# Etch_a_Sketch.net
KiCad netlist of a schematic drawn in EAGLE
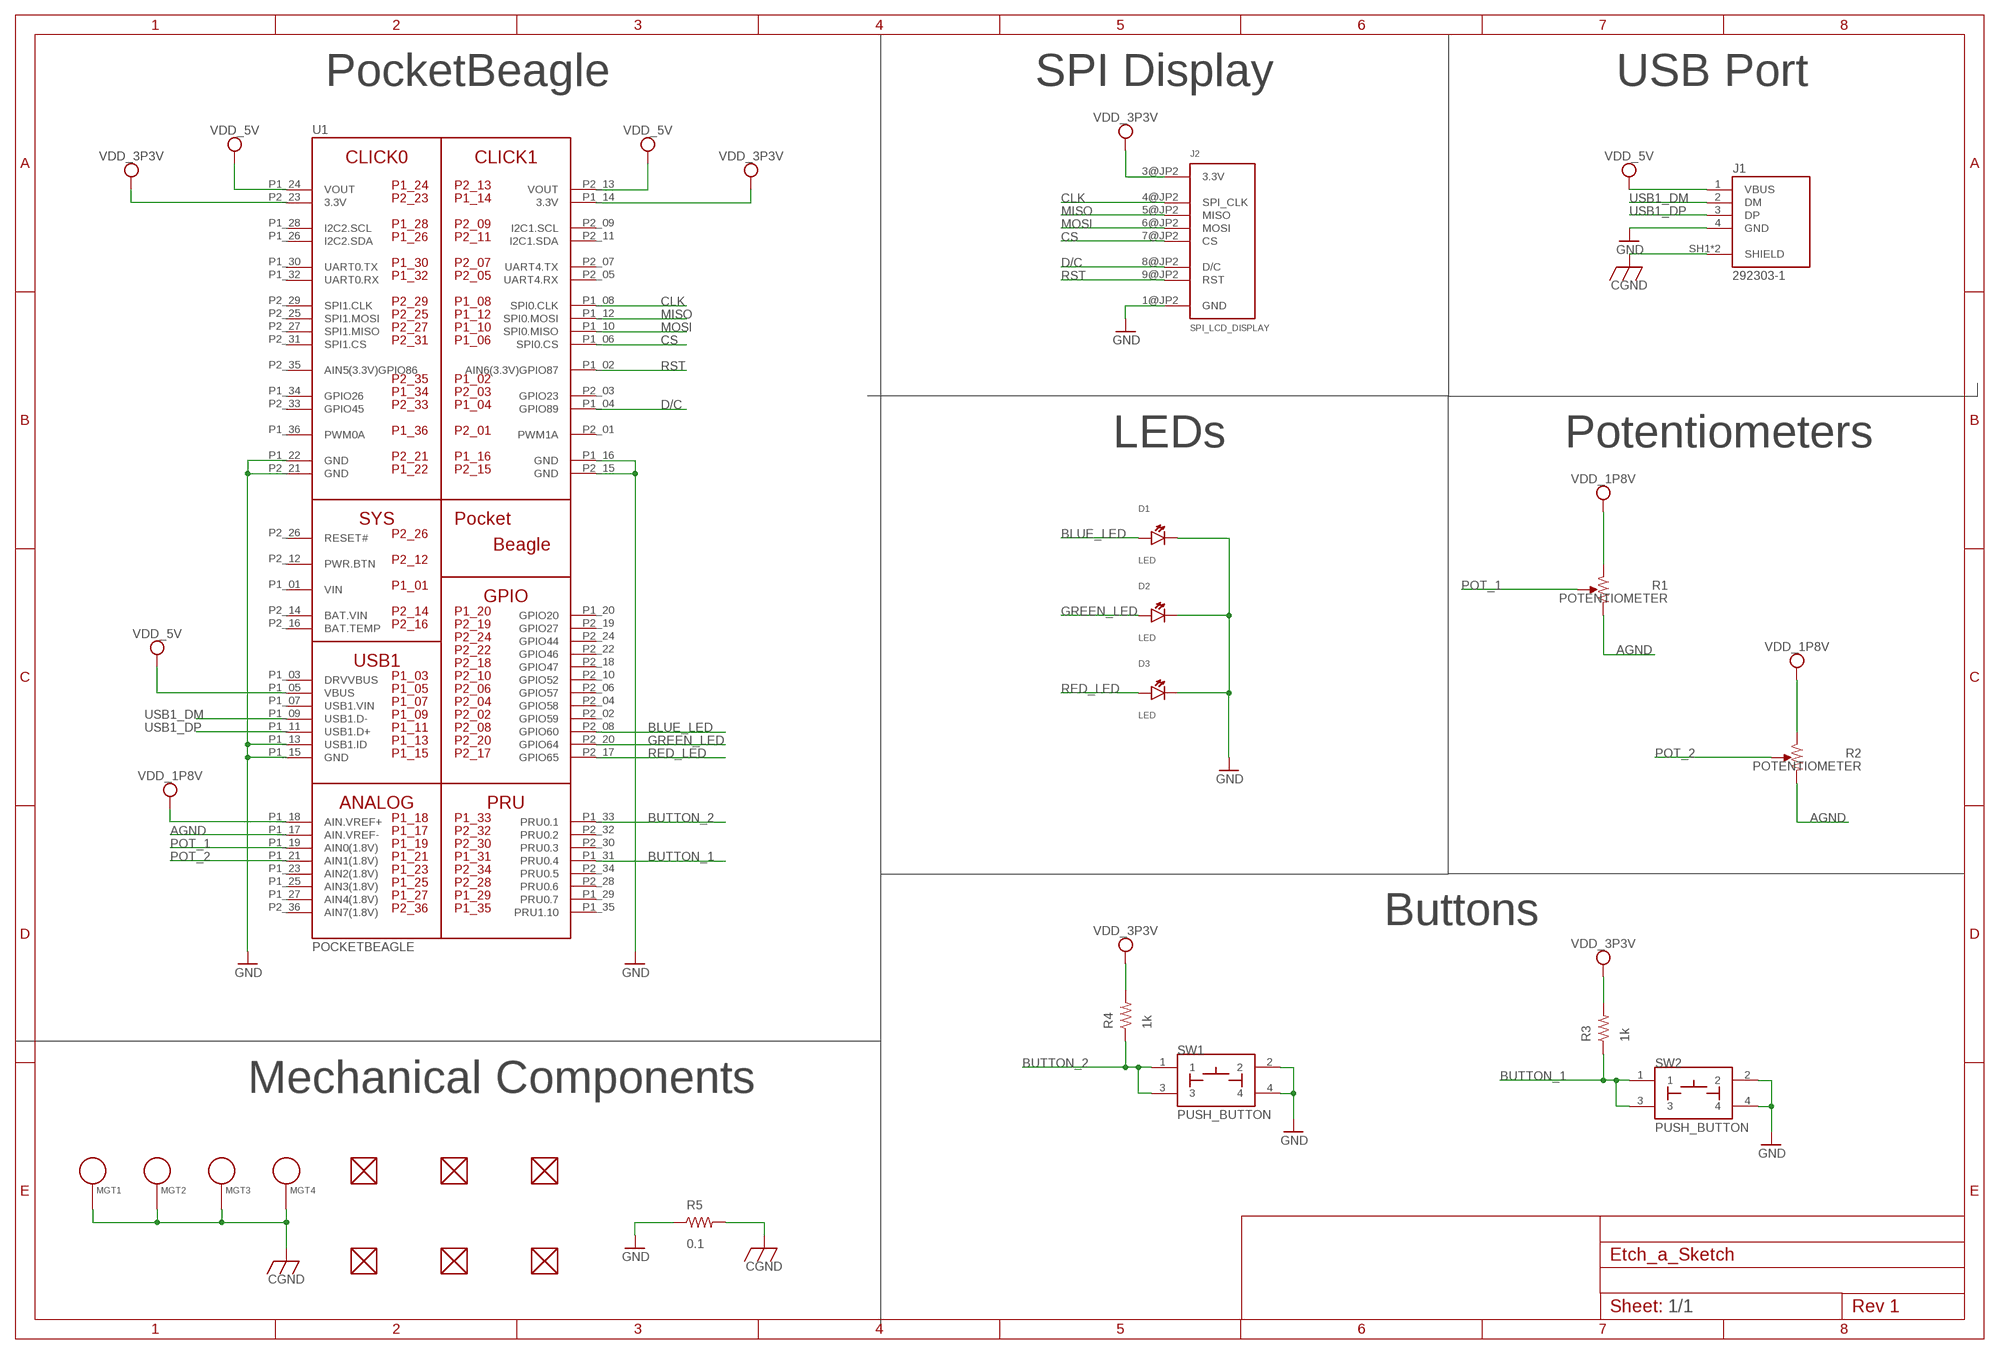
[diagram p0: schematic, sheet 1]

(export (version "E")
  (design (tool "Eeschema 10.0.6"))
  (components
    (comp (ref "D1")
      (value "LED")
      (footprint "eagle-import:EIA-STD")
      (libsource (lib "eagle-import") (part "LED"))
    )
    (comp (ref "D2")
      (value "LED")
      (footprint "eagle-import:EIA-STD")
      (libsource (lib "eagle-import") (part "LED"))
    )
    (comp (ref "D3")
      (value "LED")
      (footprint "eagle-import:EIA-STD")
      (libsource (lib "eagle-import") (part "LED"))
    )
    (comp (ref "FUD1")
      (value "FIDUCIAL")
      (footprint "eagle-import:FIDUCIAL_40MIL")
      (libsource (lib "eagle-import") (part "FIDUCIAL"))
    )
    (comp (ref "FUD2")
      (value "FIDUCIAL")
      (footprint "eagle-import:FIDUCIAL_40MIL")
      (libsource (lib "eagle-import") (part "FIDUCIAL"))
    )
    (comp (ref "FUD3")
      (value "FIDUCIAL")
      (footprint "eagle-import:FIDUCIAL_40MIL")
      (libsource (lib "eagle-import") (part "FIDUCIAL"))
    )
    (comp (ref "FUD4")
      (value "FIDUCIAL")
      (footprint "eagle-import:FIDUCIAL_40MIL")
      (libsource (lib "eagle-import") (part "FIDUCIAL"))
    )
    (comp (ref "FUD5")
      (value "FIDUCIAL")
      (footprint "eagle-import:FIDUCIAL_40MIL")
      (libsource (lib "eagle-import") (part "FIDUCIAL"))
    )
    (comp (ref "FUD6")
      (value "FIDUCIAL")
      (footprint "eagle-import:FIDUCIAL_40MIL")
      (libsource (lib "eagle-import") (part "FIDUCIAL"))
    )
    (comp (ref "J1")
      (value "292303-1")
      (footprint "eagle-import:TE_292303-1")
      (fields (field (name "MF") "TE Connectivity"))
      (libsource (lib "eagle-import") (part "292303-1"))
    )
    (comp (ref "J2")
      (value "SPI_LCD_DISPLAY")
      (footprint "eagle-import:SPI_LCD_DISPLAY")
      (libsource (lib "eagle-import") (part "SPI_LCD_DISPLAY"))
    )
    (comp (ref "MGT1")
      (value "MOUNTING_HOLE")
      (footprint "eagle-import:MOUNTING_HOLE")
      (libsource (lib "eagle-import") (part "MOUNTING_HOLE"))
    )
    (comp (ref "MGT2")
      (value "MOUNTING_HOLE")
      (footprint "eagle-import:MOUNTING_HOLE")
      (libsource (lib "eagle-import") (part "MOUNTING_HOLE"))
    )
    (comp (ref "MGT3")
      (value "MOUNTING_HOLE")
      (footprint "eagle-import:MOUNTING_HOLE")
      (libsource (lib "eagle-import") (part "MOUNTING_HOLE"))
    )
    (comp (ref "MGT4")
      (value "MOUNTING_HOLE")
      (footprint "eagle-import:MOUNTING_HOLE")
      (libsource (lib "eagle-import") (part "MOUNTING_HOLE"))
    )
    (comp (ref "R1")
      (value "POTENTIOMETER")
      (footprint "eagle-import:POT-PO90S")
      (libsource (lib "eagle-import") (part "POTENTIOMETER"))
    )
    (comp (ref "R2")
      (value "POTENTIOMETER")
      (footprint "eagle-import:POT-PO90S")
      (libsource (lib "eagle-import") (part "POTENTIOMETER"))
    )
    (comp (ref "R3")
      (value "1k")
      (footprint "eagle-import:R0603")
      (libsource (lib "eagle-import") (part "R_R0603"))
    )
    (comp (ref "R4")
      (value "1k")
      (footprint "eagle-import:R0603")
      (libsource (lib "eagle-import") (part "R_R0603"))
    )
    (comp (ref "R5")
      (value "0.1")
      (footprint "eagle-import:R0603")
      (libsource (lib "eagle-import") (part "R_R0603"))
    )
    (comp (ref "SW1")
      (value "PUSH_BUTTON")
      (footprint "eagle-import:BUTTON_12.5MM")
      (libsource (lib "eagle-import") (part "PUSH_BUTTON"))
    )
    (comp (ref "SW2")
      (value "PUSH_BUTTON")
      (footprint "eagle-import:BUTTON_12.5MM")
      (libsource (lib "eagle-import") (part "PUSH_BUTTON"))
    )
    (comp (ref "U1")
      (value "POCKETBEAGLE")
      (footprint "eagle-import:POCKETBEAGLE")
      (libsource (lib "eagle-import") (part "POCKETBEAGLE"))
    )
  )
  (nets
    (net (code "1") (name "/AGND") (class "Default")
      (node (ref "R1") (pin "CW") (pinfunction "CW_CW") (pintype "passive"))
      (node (ref "R2") (pin "CW") (pinfunction "CW_CW") (pintype "passive"))
      (node (ref "U1") (pin "P1_17") (pinfunction "AIN.VREF-_P1_17") (pintype "input"))
    )
    (net (code "2") (name "/BAT.VIN") (class "Default")
      (node (ref "U1") (pin "P2_14") (pinfunction "BAT.VIN_P2_14") (pintype "power_in"))
    )
    (net (code "3") (name "/BLUE_LED") (class "Default")
      (node (ref "D1") (pin "ANODE") (pinfunction "ANODE_ANODE") (pintype "bidirectional"))
      (node (ref "U1") (pin "P2_08") (pinfunction "GPIO60_P2_08") (pintype "bidirectional"))
    )
    (net (code "4") (name "/BUTTON_1") (class "Default")
      (node (ref "R3") (pin "1") (pinfunction "1_1") (pintype "passive"))
      (node (ref "SW2") (pin "1") (pinfunction "1_1") (pintype "bidirectional"))
      (node (ref "SW2") (pin "3") (pinfunction "3_3") (pintype "bidirectional"))
      (node (ref "U1") (pin "P1_31") (pinfunction "PRU0.4_P1_31") (pintype "bidirectional"))
    )
    (net (code "5") (name "/BUTTON_2") (class "Default")
      (node (ref "R4") (pin "1") (pinfunction "1_1") (pintype "passive"))
      (node (ref "SW1") (pin "1") (pinfunction "1_1") (pintype "bidirectional"))
      (node (ref "SW1") (pin "3") (pinfunction "3_3") (pintype "bidirectional"))
      (node (ref "U1") (pin "P1_33") (pinfunction "PRU0.1_P1_33") (pintype "bidirectional"))
    )
    (net (code "6") (name "/CLK") (class "Default")
      (node (ref "J2") (pin "4@JP2") (pinfunction "SPI_CLK_4@JP2") (pintype "bidirectional"))
      (node (ref "U1") (pin "P1_08") (pinfunction "SPI0.CLK_P1_08") (pintype "bidirectional"))
    )
    (net (code "7") (name "/CS") (class "Default")
      (node (ref "J2") (pin "7@JP2") (pinfunction "CS_7@JP2") (pintype "bidirectional"))
      (node (ref "U1") (pin "P1_06") (pinfunction "SPI0.CS_P1_06") (pintype "bidirectional"))
    )
    (net (code "8") (name "/D{slash}C") (class "Default")
      (node (ref "J2") (pin "8@JP2") (pinfunction "D/C_8@JP2") (pintype "bidirectional"))
      (node (ref "U1") (pin "P1_04") (pinfunction "GPIO89_P1_04") (pintype "bidirectional"))
    )
    (net (code "9") (name "/GREEN_LED") (class "Default")
      (node (ref "D2") (pin "ANODE") (pinfunction "ANODE_ANODE") (pintype "bidirectional"))
      (node (ref "U1") (pin "P2_20") (pinfunction "GPIO64_P2_20") (pintype "bidirectional"))
    )
    (net (code "10") (name "/MISO") (class "Default")
      (node (ref "J2") (pin "5@JP2") (pinfunction "MISO_5@JP2") (pintype "bidirectional"))
      (node (ref "U1") (pin "P1_12") (pinfunction "SPI0.MOSI_P1_12") (pintype "bidirectional"))
    )
    (net (code "11") (name "/MOSI") (class "Default")
      (node (ref "J2") (pin "6@JP2") (pinfunction "MOSI_6@JP2") (pintype "bidirectional"))
      (node (ref "U1") (pin "P1_10") (pinfunction "SPI0.MISO_P1_10") (pintype "bidirectional"))
    )
    (net (code "12") (name "/POT_1") (class "Default")
      (node (ref "R1") (pin "S") (pinfunction "S_S") (pintype "bidirectional"))
      (node (ref "U1") (pin "P1_19") (pinfunction "AIN0(1.8V)_P1_19") (pintype "input"))
    )
    (net (code "13") (name "/POT_2") (class "Default")
      (node (ref "R2") (pin "S") (pinfunction "S_S") (pintype "bidirectional"))
      (node (ref "U1") (pin "P1_21") (pinfunction "AIN1(1.8V)_P1_21") (pintype "input"))
    )
    (net (code "14") (name "/RED_LED") (class "Default")
      (node (ref "D3") (pin "ANODE") (pinfunction "ANODE_ANODE") (pintype "bidirectional"))
      (node (ref "U1") (pin "P2_17") (pinfunction "GPIO65_P2_17") (pintype "bidirectional"))
    )
    (net (code "15") (name "/RST") (class "Default")
      (node (ref "J2") (pin "9@JP2") (pinfunction "RST_9@JP2") (pintype "bidirectional"))
      (node (ref "U1") (pin "P1_02") (pinfunction "AIN6(3.3V)GPIO87_P1_02") (pintype "bidirectional"))
    )
    (net (code "16") (name "/USB1_DM") (class "Default")
      (node (ref "J1") (pin "2") (pinfunction "DM_2") (pintype "passive"))
      (node (ref "U1") (pin "P1_09") (pinfunction "USB1.D-_P1_09") (pintype "bidirectional"))
    )
    (net (code "17") (name "/USB1_DP") (class "Default")
      (node (ref "J1") (pin "3") (pinfunction "DP_3") (pintype "passive"))
      (node (ref "U1") (pin "P1_11") (pinfunction "USB1.D+_P1_11") (pintype "bidirectional"))
    )
    (net (code "18") (name "/VIN") (class "Default")
      (node (ref "U1") (pin "P1_01") (pinfunction "VIN_P1_01") (pintype "power_in"))
    )
    (net (code "19") (name "CGND") (class "Default")
      (node (ref "J1") (pin "SH1") (pinfunction "SHIELD_SH1") (pintype "passive"))
      (node (ref "J1") (pin "SH2") (pinfunction "SHIELD_SH2") (pintype "passive"))
      (node (ref "MGT1") (pin "P$1") (pinfunction "P$1_P$1") (pintype "bidirectional"))
      (node (ref "MGT2") (pin "P$1") (pinfunction "P$1_P$1") (pintype "bidirectional"))
      (node (ref "MGT3") (pin "P$1") (pinfunction "P$1_P$1") (pintype "bidirectional"))
      (node (ref "MGT4") (pin "P$1") (pinfunction "P$1_P$1") (pintype "bidirectional"))
      (node (ref "R5") (pin "2") (pinfunction "2_2") (pintype "passive"))
    )
    (net (code "20") (name "GND") (class "Default")
      (node (ref "D1") (pin "CATHODE") (pinfunction "CATHODE_CATHODE") (pintype "bidirectional"))
      (node (ref "D2") (pin "CATHODE") (pinfunction "CATHODE_CATHODE") (pintype "bidirectional"))
      (node (ref "D3") (pin "CATHODE") (pinfunction "CATHODE_CATHODE") (pintype "bidirectional"))
      (node (ref "J1") (pin "4") (pinfunction "GND_4") (pintype "passive"))
      (node (ref "J2") (pin "1@JP2") (pinfunction "GND_1@JP2") (pintype "bidirectional"))
      (node (ref "R5") (pin "1") (pinfunction "1_1") (pintype "passive"))
      (node (ref "SW1") (pin "2") (pinfunction "2_2") (pintype "bidirectional"))
      (node (ref "SW1") (pin "4") (pinfunction "4_4") (pintype "bidirectional"))
      (node (ref "SW2") (pin "2") (pinfunction "2_2") (pintype "bidirectional"))
      (node (ref "SW2") (pin "4") (pinfunction "4_4") (pintype "bidirectional"))
      (node (ref "U1") (pin "P1_13") (pinfunction "USB1.ID_P1_13") (pintype "bidirectional"))
      (node (ref "U1") (pin "P1_15") (pinfunction "GND_P1_15") (pintype "bidirectional"))
      (node (ref "U1") (pin "P1_16") (pinfunction "GND_P1_16") (pintype "power_in"))
      (node (ref "U1") (pin "P1_22") (pinfunction "GND_P1_22") (pintype "power_in"))
      (node (ref "U1") (pin "P2_15") (pinfunction "GND_P2_15") (pintype "power_in"))
      (node (ref "U1") (pin "P2_21") (pinfunction "GND_P2_21") (pintype "power_in"))
    )
    (net (code "21") (name "VDD_1P8V") (class "Default")
      (node (ref "R1") (pin "CCW") (pinfunction "CCW_CCW") (pintype "passive"))
      (node (ref "R2") (pin "CCW") (pinfunction "CCW_CCW") (pintype "passive"))
      (node (ref "U1") (pin "P1_18") (pinfunction "AIN.VREF+_P1_18") (pintype "input"))
    )
    (net (code "22") (name "VDD_3P3V") (class "Default")
      (node (ref "J2") (pin "3@JP2") (pinfunction "3.3V_3@JP2") (pintype "bidirectional"))
      (node (ref "R3") (pin "2") (pinfunction "2_2") (pintype "passive"))
      (node (ref "R4") (pin "2") (pinfunction "2_2") (pintype "passive"))
      (node (ref "U1") (pin "P1_14") (pinfunction "3.3V_P1_14") (pintype "power_in"))
      (node (ref "U1") (pin "P2_23") (pinfunction "3.3V_P2_23") (pintype "power_in"))
    )
    (net (code "23") (name "VDD_5V") (class "Default")
      (node (ref "J1") (pin "1") (pinfunction "VBUS_1") (pintype "passive"))
      (node (ref "U1") (pin "P1_05") (pinfunction "VBUS_P1_05") (pintype "bidirectional"))
      (node (ref "U1") (pin "P1_24") (pinfunction "VOUT_P1_24") (pintype "power_in"))
      (node (ref "U1") (pin "P2_13") (pinfunction "VOUT_P2_13") (pintype "power_in"))
    )
    (net (code "24") (name "unconnected-(FUD1-PadP$1)") (class "Default")
      (node (ref "FUD1") (pin "P$1") (pinfunction "P$1_P$1") (pintype "no_connect"))
    )
    (net (code "25") (name "unconnected-(FUD2-PadP$1)") (class "Default")
      (node (ref "FUD2") (pin "P$1") (pinfunction "P$1_P$1") (pintype "no_connect"))
    )
    (net (code "26") (name "unconnected-(FUD3-PadP$1)") (class "Default")
      (node (ref "FUD3") (pin "P$1") (pinfunction "P$1_P$1") (pintype "no_connect"))
    )
    (net (code "27") (name "unconnected-(FUD4-PadP$1)") (class "Default")
      (node (ref "FUD4") (pin "P$1") (pinfunction "P$1_P$1") (pintype "no_connect"))
    )
    (net (code "28") (name "unconnected-(FUD5-PadP$1)") (class "Default")
      (node (ref "FUD5") (pin "P$1") (pinfunction "P$1_P$1") (pintype "no_connect"))
    )
    (net (code "29") (name "unconnected-(FUD6-PadP$1)") (class "Default")
      (node (ref "FUD6") (pin "P$1") (pinfunction "P$1_P$1") (pintype "no_connect"))
    )
    (net (code "30") (name "unconnected-(U1-AIN2(1.8V)-PadP1_23)") (class "Default")
      (node (ref "U1") (pin "P1_23") (pinfunction "AIN2(1.8V)_P1_23") (pintype "input"))
    )
    (net (code "31") (name "unconnected-(U1-AIN3(1.8V)-PadP1_25)") (class "Default")
      (node (ref "U1") (pin "P1_25") (pinfunction "AIN3(1.8V)_P1_25") (pintype "input"))
    )
    (net (code "32") (name "unconnected-(U1-AIN4(1.8V)-PadP1_27)") (class "Default")
      (node (ref "U1") (pin "P1_27") (pinfunction "AIN4(1.8V)_P1_27") (pintype "input"))
    )
    (net (code "33") (name "unconnected-(U1-AIN5(3.3V)GPIO86-PadP2_35)") (class "Default")
      (node (ref "U1") (pin "P2_35") (pinfunction "AIN5(3.3V)GPIO86_P2_35") (pintype "bidirectional"))
    )
    (net (code "34") (name "unconnected-(U1-AIN7(1.8V)-PadP2_36)") (class "Default")
      (node (ref "U1") (pin "P2_36") (pinfunction "AIN7(1.8V)_P2_36") (pintype "input"))
    )
    (net (code "35") (name "unconnected-(U1-BAT.TEMP-PadP2_16)") (class "Default")
      (node (ref "U1") (pin "P2_16") (pinfunction "BAT.TEMP_P2_16") (pintype "input"))
    )
    (net (code "36") (name "unconnected-(U1-DRVVBUS-PadP1_03)") (class "Default")
      (node (ref "U1") (pin "P1_03") (pinfunction "DRVVBUS_P1_03") (pintype "bidirectional"))
    )
    (net (code "37") (name "unconnected-(U1-GPIO20-PadP1_20)") (class "Default")
      (node (ref "U1") (pin "P1_20") (pinfunction "GPIO20_P1_20") (pintype "bidirectional"))
    )
    (net (code "38") (name "unconnected-(U1-GPIO23-PadP2_03)") (class "Default")
      (node (ref "U1") (pin "P2_03") (pinfunction "GPIO23_P2_03") (pintype "bidirectional"))
    )
    (net (code "39") (name "unconnected-(U1-GPIO26-PadP1_34)") (class "Default")
      (node (ref "U1") (pin "P1_34") (pinfunction "GPIO26_P1_34") (pintype "bidirectional"))
    )
    (net (code "40") (name "unconnected-(U1-GPIO27-PadP2_19)") (class "Default")
      (node (ref "U1") (pin "P2_19") (pinfunction "GPIO27_P2_19") (pintype "bidirectional"))
    )
    (net (code "41") (name "unconnected-(U1-GPIO44-PadP2_24)") (class "Default")
      (node (ref "U1") (pin "P2_24") (pinfunction "GPIO44_P2_24") (pintype "bidirectional"))
    )
    (net (code "42") (name "unconnected-(U1-GPIO45-PadP2_33)") (class "Default")
      (node (ref "U1") (pin "P2_33") (pinfunction "GPIO45_P2_33") (pintype "bidirectional"))
    )
    (net (code "43") (name "unconnected-(U1-GPIO46-PadP2_22)") (class "Default")
      (node (ref "U1") (pin "P2_22") (pinfunction "GPIO46_P2_22") (pintype "bidirectional"))
    )
    (net (code "44") (name "unconnected-(U1-GPIO47-PadP2_18)") (class "Default")
      (node (ref "U1") (pin "P2_18") (pinfunction "GPIO47_P2_18") (pintype "bidirectional"))
    )
    (net (code "45") (name "unconnected-(U1-GPIO52-PadP2_10)") (class "Default")
      (node (ref "U1") (pin "P2_10") (pinfunction "GPIO52_P2_10") (pintype "bidirectional"))
    )
    (net (code "46") (name "unconnected-(U1-GPIO57-PadP2_06)") (class "Default")
      (node (ref "U1") (pin "P2_06") (pinfunction "GPIO57_P2_06") (pintype "bidirectional"))
    )
    (net (code "47") (name "unconnected-(U1-GPIO58-PadP2_04)") (class "Default")
      (node (ref "U1") (pin "P2_04") (pinfunction "GPIO58_P2_04") (pintype "bidirectional"))
    )
    (net (code "48") (name "unconnected-(U1-GPIO59-PadP2_02)") (class "Default")
      (node (ref "U1") (pin "P2_02") (pinfunction "GPIO59_P2_02") (pintype "bidirectional"))
    )
    (net (code "49") (name "unconnected-(U1-I2C1.SCL-PadP2_09)") (class "Default")
      (node (ref "U1") (pin "P2_09") (pinfunction "I2C1.SCL_P2_09") (pintype "bidirectional"))
    )
    (net (code "50") (name "unconnected-(U1-I2C1.SDA-PadP2_11)") (class "Default")
      (node (ref "U1") (pin "P2_11") (pinfunction "I2C1.SDA_P2_11") (pintype "bidirectional"))
    )
    (net (code "51") (name "unconnected-(U1-I2C2.SCL-PadP1_28)") (class "Default")
      (node (ref "U1") (pin "P1_28") (pinfunction "I2C2.SCL_P1_28") (pintype "bidirectional"))
    )
    (net (code "52") (name "unconnected-(U1-I2C2.SDA-PadP1_26)") (class "Default")
      (node (ref "U1") (pin "P1_26") (pinfunction "I2C2.SDA_P1_26") (pintype "bidirectional"))
    )
    (net (code "53") (name "unconnected-(U1-PRU0.2-PadP2_32)") (class "Default")
      (node (ref "U1") (pin "P2_32") (pinfunction "PRU0.2_P2_32") (pintype "bidirectional"))
    )
    (net (code "54") (name "unconnected-(U1-PRU0.3-PadP2_30)") (class "Default")
      (node (ref "U1") (pin "P2_30") (pinfunction "PRU0.3_P2_30") (pintype "bidirectional"))
    )
    (net (code "55") (name "unconnected-(U1-PRU0.5-PadP2_34)") (class "Default")
      (node (ref "U1") (pin "P2_34") (pinfunction "PRU0.5_P2_34") (pintype "bidirectional"))
    )
    (net (code "56") (name "unconnected-(U1-PRU0.6-PadP2_28)") (class "Default")
      (node (ref "U1") (pin "P2_28") (pinfunction "PRU0.6_P2_28") (pintype "bidirectional"))
    )
    (net (code "57") (name "unconnected-(U1-PRU0.7-PadP1_29)") (class "Default")
      (node (ref "U1") (pin "P1_29") (pinfunction "PRU0.7_P1_29") (pintype "bidirectional"))
    )
    (net (code "58") (name "unconnected-(U1-PRU1.10-PadP1_35)") (class "Default")
      (node (ref "U1") (pin "P1_35") (pinfunction "PRU1.10_P1_35") (pintype "bidirectional"))
    )
    (net (code "59") (name "unconnected-(U1-PWM0A-PadP1_36)") (class "Default")
      (node (ref "U1") (pin "P1_36") (pinfunction "PWM0A_P1_36") (pintype "bidirectional"))
    )
    (net (code "60") (name "unconnected-(U1-PWM1A-PadP2_01)") (class "Default")
      (node (ref "U1") (pin "P2_01") (pinfunction "PWM1A_P2_01") (pintype "bidirectional"))
    )
    (net (code "61") (name "unconnected-(U1-PWR.BTN-PadP2_12)") (class "Default")
      (node (ref "U1") (pin "P2_12") (pinfunction "PWR.BTN_P2_12") (pintype "input"))
    )
    (net (code "62") (name "unconnected-(U1-RESET#-PadP2_26)") (class "Default")
      (node (ref "U1") (pin "P2_26") (pinfunction "RESET#_P2_26") (pintype "input"))
    )
    (net (code "63") (name "unconnected-(U1-SPI1.CLK-PadP2_29)") (class "Default")
      (node (ref "U1") (pin "P2_29") (pinfunction "SPI1.CLK_P2_29") (pintype "bidirectional"))
    )
    (net (code "64") (name "unconnected-(U1-SPI1.CS-PadP2_31)") (class "Default")
      (node (ref "U1") (pin "P2_31") (pinfunction "SPI1.CS_P2_31") (pintype "bidirectional"))
    )
    (net (code "65") (name "unconnected-(U1-SPI1.MISO-PadP2_27)") (class "Default")
      (node (ref "U1") (pin "P2_27") (pinfunction "SPI1.MISO_P2_27") (pintype "bidirectional"))
    )
    (net (code "66") (name "unconnected-(U1-SPI1.MOSI-PadP2_25)") (class "Default")
      (node (ref "U1") (pin "P2_25") (pinfunction "SPI1.MOSI_P2_25") (pintype "bidirectional"))
    )
    (net (code "67") (name "unconnected-(U1-UART0.RX-PadP1_32)") (class "Default")
      (node (ref "U1") (pin "P1_32") (pinfunction "UART0.RX_P1_32") (pintype "bidirectional"))
    )
    (net (code "68") (name "unconnected-(U1-UART0.TX-PadP1_30)") (class "Default")
      (node (ref "U1") (pin "P1_30") (pinfunction "UART0.TX_P1_30") (pintype "bidirectional"))
    )
    (net (code "69") (name "unconnected-(U1-UART4.RX-PadP2_05)") (class "Default")
      (node (ref "U1") (pin "P2_05") (pinfunction "UART4.RX_P2_05") (pintype "bidirectional"))
    )
    (net (code "70") (name "unconnected-(U1-UART4.TX-PadP2_07)") (class "Default")
      (node (ref "U1") (pin "P2_07") (pinfunction "UART4.TX_P2_07") (pintype "bidirectional"))
    )
    (net (code "71") (name "unconnected-(U1-USB1.VIN-PadP1_07)") (class "Default")
      (node (ref "U1") (pin "P1_07") (pinfunction "USB1.VIN_P1_07") (pintype "bidirectional"))
    )
  )
)
